# TDC_VTUNE_DAC.net
KiCad netlist of a schematic drawn in Altium Designer
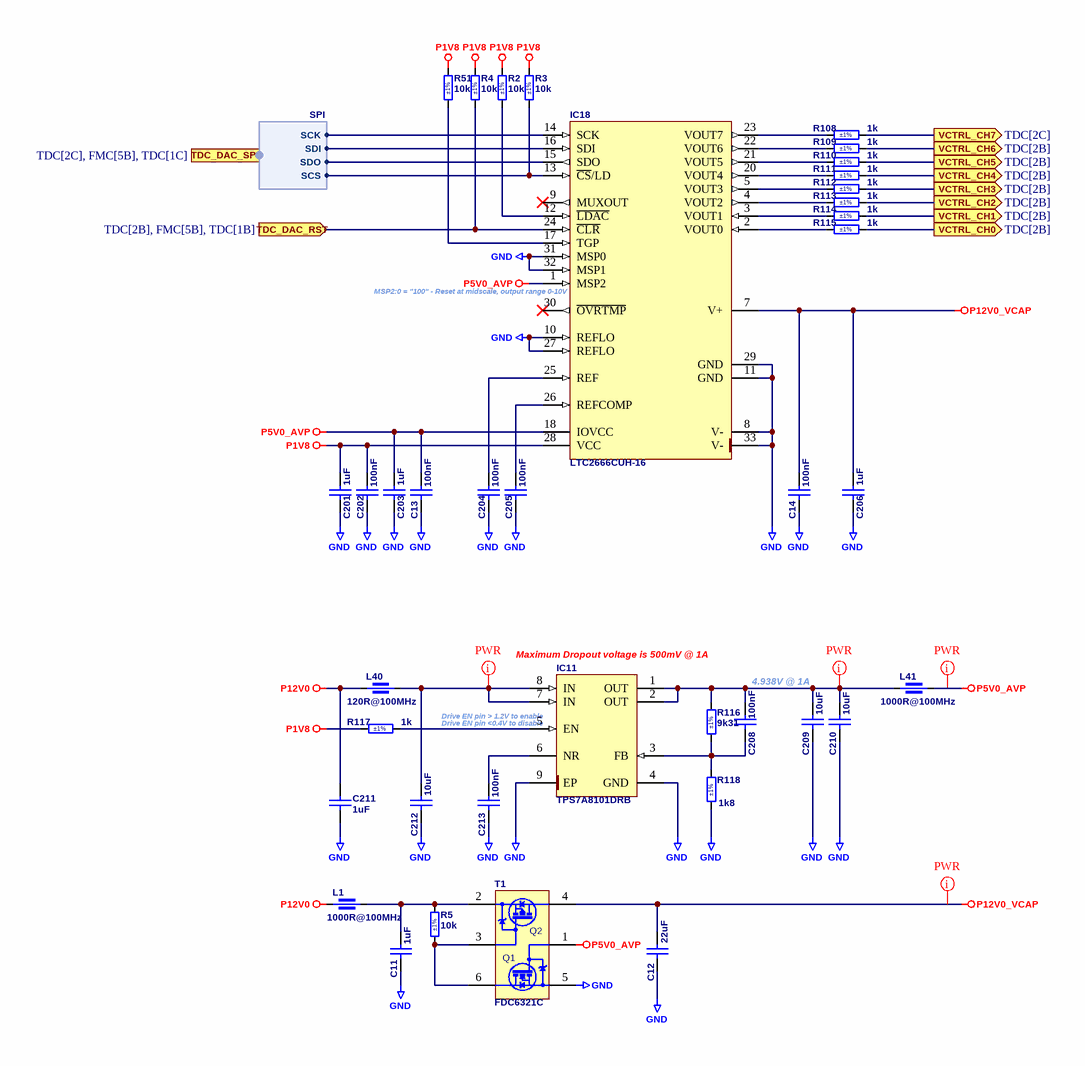
[diagram p0: TDC_VTUNE_DAC.SchDoc]

(export (version "E")
  (design (tool "Eeschema 10.0.6"))
  (components
    (comp (ref "C11")
      (value "1uF")
      (footprint "CAPC1005X55N")
      (description "Non-polarised capacitor")
      (fields
        (field (name "PART NUMBER") "CC0402_1UF_16V_10%_X5R")
        (field (name "VOLTAGE") "16V")
        (field (name "AUTHOR") "CERN DEM JLC")
      )
      (libsource (lib "Capacitors") (part "Capacitor - non polarized"))
    )
    (comp (ref "C12")
      (value "22uF")
      (footprint "CAPC2012X135N")
      (description "Non-polarised capacitor")
      (fields
        (field (name "MANUFACTURER PART NUMBER") "CC0805_22UF_16V_10%_X5R")
        (field (name "MANUFACTURER") "GENERIC")
        (field (name "AUTHOR") "CERN DEM JLC")
      )
      (libsource (lib "Capacitors") (part "Capacitor - non polarized"))
    )
    (comp (ref "C13")
      (value "100nF")
      (footprint "CAPC1005X55N")
      (description "Non-polarised capacitor")
      (fields
        (field (name "PART NUMBER") "CC0402_100NF_16V_10%_X5R")
        (field (name "VOLTAGE") "16V")
        (field (name "AUTHOR") "CERN DEM JLC")
      )
      (libsource (lib "Capacitors") (part "Capacitor - non polarized"))
    )
    (comp (ref "C14")
      (value "100nF")
      (footprint "CAPC1005X55N")
      (description "Non-polarised capacitor")
      (fields
        (field (name "PART NUMBER") "CC0402_100NF_16V_10%_X5R")
        (field (name "VOLTAGE") "16V")
        (field (name "AUTHOR") "CERN DEM JLC")
      )
      (libsource (lib "Capacitors") (part "Capacitor - non polarized"))
    )
    (comp (ref "C201")
      (value "1uF")
      (footprint "CAPC1608X87N")
      (description "Non-polarised capacitor")
      (fields
        (field (name "PART NUMBER") "CC0603_1UF_25V_10%_X7R")
        (field (name "VOLTAGE") "25V")
        (field (name "AUTHOR") "CERN DEM JLC")
      )
      (libsource (lib "Capacitors") (part "Capacitor - non polarized"))
    )
    (comp (ref "C202")
      (value "100nF")
      (footprint "CAPC1005X55N")
      (description "Non-polarised capacitor")
      (fields
        (field (name "PART NUMBER") "CC0402_100NF_16V_10%_X5R")
        (field (name "VOLTAGE") "16V")
        (field (name "AUTHOR") "CERN DEM JLC")
      )
      (libsource (lib "Capacitors") (part "Capacitor - non polarized"))
    )
    (comp (ref "C203")
      (value "1uF")
      (footprint "CAPC1608X87N")
      (description "Non-polarised capacitor")
      (fields
        (field (name "PART NUMBER") "CC0603_1UF_25V_10%_X7R")
        (field (name "VOLTAGE") "25V")
        (field (name "AUTHOR") "CERN DEM JLC")
      )
      (libsource (lib "Capacitors") (part "Capacitor - non polarized"))
    )
    (comp (ref "C204")
      (value "100nF")
      (footprint "CAPC1005X55N")
      (description "Non-polarised capacitor")
      (fields
        (field (name "PART NUMBER") "CC0402_100NF_16V_10%_X5R")
        (field (name "VOLTAGE") "16V")
        (field (name "AUTHOR") "CERN DEM JLC")
      )
      (libsource (lib "Capacitors") (part "Capacitor - non polarized"))
    )
    (comp (ref "C205")
      (value "100nF")
      (footprint "CAPC1005X55N")
      (description "Non-polarised capacitor")
      (fields
        (field (name "PART NUMBER") "CC0402_100NF_16V_10%_X5R")
        (field (name "VOLTAGE") "16V")
        (field (name "AUTHOR") "CERN DEM JLC")
      )
      (libsource (lib "Capacitors") (part "Capacitor - non polarized"))
    )
    (comp (ref "C206")
      (value "1uF")
      (footprint "CAPC1608X87N")
      (description "Non-polarised capacitor")
      (fields
        (field (name "PART NUMBER") "CC0603_1UF_25V_10%_X7R")
        (field (name "VOLTAGE") "25V")
        (field (name "AUTHOR") "CERN DEM JLC")
      )
      (libsource (lib "Capacitors") (part "Capacitor - non polarized"))
    )
    (comp (ref "C208")
      (value "100nF")
      (footprint "CAPC1005X55N")
      (description "Non-polarised capacitor")
      (fields
        (field (name "PART NUMBER") "CC0402_100NF_16V_10%_X5R")
        (field (name "VOLTAGE") "16V")
        (field (name "AUTHOR") "CERN DEM JLC")
      )
      (libsource (lib "Capacitors") (part "Capacitor - non polarized"))
    )
    (comp (ref "C209")
      (value "10uF")
      (footprint "CAPC1608X90N")
      (description "Non-polarised capacitor")
      (fields
        (field (name "PART NUMBER") "CC0603_10UF_16V_10%_X5R_MURATA_GRT188R61C106KE13")
        (field (name "VOLTAGE") "16V")
        (field (name "AUTHOR") "CERN DEM HF")
      )
      (libsource (lib "Capacitors") (part "Capacitor - non polarized"))
    )
    (comp (ref "C210")
      (value "10uF")
      (footprint "CAPC1608X90N")
      (description "Non-polarised capacitor")
      (fields
        (field (name "PART NUMBER") "CC0603_10UF_16V_10%_X5R_MURATA_GRT188R61C106KE13")
        (field (name "VOLTAGE") "16V")
        (field (name "AUTHOR") "CERN DEM HF")
      )
      (libsource (lib "Capacitors") (part "Capacitor - non polarized"))
    )
    (comp (ref "C211")
      (value "1uF")
      (footprint "CAPC1005X55N")
      (description "Non-polarised capacitor")
      (fields
        (field (name "PART NUMBER") "CC0402_1UF_16V_10%_X5R")
        (field (name "VOLTAGE") "16V")
        (field (name "AUTHOR") "CERN DEM JLC")
      )
      (libsource (lib "Capacitors") (part "Capacitor - non polarized"))
    )
    (comp (ref "C212")
      (value "10uF")
      (footprint "CAPC1608X90N")
      (description "Non-polarised capacitor")
      (fields
        (field (name "PART NUMBER") "CC0603_10UF_16V_10%_X5R_MURATA_GRT188R61C106KE13")
        (field (name "VOLTAGE") "16V")
        (field (name "AUTHOR") "CERN DEM HF")
      )
      (libsource (lib "Capacitors") (part "Capacitor - non polarized"))
    )
    (comp (ref "C213")
      (value "100nF")
      (footprint "CAPC1005X55N")
      (description "Non-polarised capacitor")
      (fields
        (field (name "PART NUMBER") "CC0402_100NF_16V_10%_X5R")
        (field (name "VOLTAGE") "16V")
        (field (name "AUTHOR") "CERN DEM JLC")
      )
      (libsource (lib "Capacitors") (part "Capacitor - non polarized"))
    )
    (comp (ref "IC11")
      (value "TPS7A8101DRB")
      (footprint "TEXAS_DRB(S-PVSON-N8)")
      (description "0.8V to 6V, 1A, Low-Noise, Wide-Bandwidth, High PSRR, Low-Dropout Linear Regulator")
      (fields (field (name "MANUFACTURER") "TEXAS INSTRUMENTS") (field (name "AUTHOR") "CERN DEM BC"))
      (libsource (lib "ICs And Semiconductors") (part "TPS7A8101DRB"))
    )
    (comp (ref "IC18")
      (value "LTC2666CUH-16")
      (footprint "QFN50P500X500X80-33N-S355")
      (description "Octal 16-Bit, ±10V Vout, SoftSpan DAC with 10ppm/°C Max Reference")
      (fields
        (field (name "PART NUMBER") "LTC2666CUH-16#PBF")
        (field (name "MANUFACTURER") "LINEAR TECHNOLOGY")
        (field (name "AUTHOR") "CERN DEM JLC")
      )
      (libsource (lib "ICs And Semiconductors") (part "LTC2666"))
    )
    (comp (ref "L1")
      (value "1000R@100MHz")
      (footprint "INDC1608X95N")
      (fields
        (field (name "PART NUMBER") "IND0603_MURATA_BLM18KG102SN1")
        (field (name "POWER") "1A")
        (field (name "TOLERANCE") "±25%")
        (field (name "AUTHOR") "CERN DEM HF")
      )
      (libsource (lib "Inductors & Transformers") (part "Ferrite Bead"))
    )
    (comp (ref "L40")
      (value "120R@100MHz")
      (footprint "INDC1005X55N")
      (fields
        (field (name "PART NUMBER") "IND0402_MURATA_BLM15PX121SN1D")
        (field (name "POWER") "2A")
        (field (name "TOLERANCE") "±25%")
        (field (name "AUTHOR") "CERN DEM JMW")
      )
      (libsource (lib "Inductors & Transformers") (part "Ferrite Bead"))
    )
    (comp (ref "L41")
      (value "1000R@100MHz")
      (footprint "INDC1608X95N")
      (fields
        (field (name "PART NUMBER") "IND0603_MURATA_BLM18KG102SN1")
        (field (name "POWER") "1A")
        (field (name "TOLERANCE") "±25%")
        (field (name "AUTHOR") "CERN DEM HF")
      )
      (libsource (lib "Inductors & Transformers") (part "Ferrite Bead"))
    )
    (comp (ref "R2")
      (value "10k")
      (footprint "RESC1005X40N")
      (description "Resistor - 1%")
      (fields
        (field (name "TOLERANCE") "±1%")
        (field (name "PART NUMBER") "R0402_10K_1%_0.0625W_100PPM")
        (field (name "POWER") "0.0625W")
        (field (name "AUTHOR") "CERN DEM JLC")
      )
      (libsource (lib "Resistors") (part "Resistor - 1%"))
    )
    (comp (ref "R3")
      (value "10k")
      (footprint "RESC1005X40N")
      (description "Resistor - 1%")
      (fields
        (field (name "TOLERANCE") "±1%")
        (field (name "PART NUMBER") "R0402_10K_1%_0.0625W_100PPM")
        (field (name "POWER") "0.0625W")
        (field (name "AUTHOR") "CERN DEM JLC")
      )
      (libsource (lib "Resistors") (part "Resistor - 1%"))
    )
    (comp (ref "R4")
      (value "10k")
      (footprint "RESC1005X40N")
      (description "Resistor - 1%")
      (fields
        (field (name "TOLERANCE") "±1%")
        (field (name "PART NUMBER") "R0402_10K_1%_0.0625W_100PPM")
        (field (name "POWER") "0.0625W")
        (field (name "AUTHOR") "CERN DEM JLC")
      )
      (libsource (lib "Resistors") (part "Resistor - 1%"))
    )
    (comp (ref "R5")
      (value "10k")
      (footprint "RESC1005X40N")
      (description "Resistor - 1%")
      (fields
        (field (name "TOLERANCE") "±1%")
        (field (name "PART NUMBER") "R0402_10K_1%_0.0625W_100PPM")
        (field (name "POWER") "0.0625W")
        (field (name "AUTHOR") "CERN DEM JLC")
      )
      (libsource (lib "Resistors") (part "Resistor - 1%"))
    )
    (comp (ref "R51")
      (value "10k")
      (footprint "RESC1005X40N")
      (description "Resistor - 1%")
      (fields
        (field (name "TOLERANCE") "±1%")
        (field (name "PART NUMBER") "R0402_10K_1%_0.0625W_100PPM")
        (field (name "POWER") "0.0625W")
        (field (name "AUTHOR") "CERN DEM JLC")
      )
      (libsource (lib "Resistors") (part "Resistor - 1%"))
    )
    (comp (ref "R108")
      (value "1k")
      (footprint "RESC1005X40N")
      (description "Resistor - 1%")
      (fields
        (field (name "TOLERANCE") "±1%")
        (field (name "PART NUMBER") "R0402_1K_1%_0.0625W_100PPM")
        (field (name "POWER") "0.0625W")
        (field (name "AUTHOR") "CERN DEM JLC")
      )
      (libsource (lib "Resistors") (part "Resistor - 1%"))
    )
    (comp (ref "R109")
      (value "1k")
      (footprint "RESC1005X40N")
      (description "Resistor - 1%")
      (fields
        (field (name "TOLERANCE") "±1%")
        (field (name "PART NUMBER") "R0402_1K_1%_0.0625W_100PPM")
        (field (name "POWER") "0.0625W")
        (field (name "AUTHOR") "CERN DEM JLC")
      )
      (libsource (lib "Resistors") (part "Resistor - 1%"))
    )
    (comp (ref "R110")
      (value "1k")
      (footprint "RESC1005X40N")
      (description "Resistor - 1%")
      (fields
        (field (name "TOLERANCE") "±1%")
        (field (name "PART NUMBER") "R0402_1K_1%_0.0625W_100PPM")
        (field (name "POWER") "0.0625W")
        (field (name "AUTHOR") "CERN DEM JLC")
      )
      (libsource (lib "Resistors") (part "Resistor - 1%"))
    )
    (comp (ref "R111")
      (value "1k")
      (footprint "RESC1005X40N")
      (description "Resistor - 1%")
      (fields
        (field (name "TOLERANCE") "±1%")
        (field (name "PART NUMBER") "R0402_1K_1%_0.0625W_100PPM")
        (field (name "POWER") "0.0625W")
        (field (name "AUTHOR") "CERN DEM JLC")
      )
      (libsource (lib "Resistors") (part "Resistor - 1%"))
    )
    (comp (ref "R112")
      (value "1k")
      (footprint "RESC1005X40N")
      (description "Resistor - 1%")
      (fields
        (field (name "TOLERANCE") "±1%")
        (field (name "PART NUMBER") "R0402_1K_1%_0.0625W_100PPM")
        (field (name "POWER") "0.0625W")
        (field (name "AUTHOR") "CERN DEM JLC")
      )
      (libsource (lib "Resistors") (part "Resistor - 1%"))
    )
    (comp (ref "R113")
      (value "1k")
      (footprint "RESC1005X40N")
      (description "Resistor - 1%")
      (fields
        (field (name "TOLERANCE") "±1%")
        (field (name "PART NUMBER") "R0402_1K_1%_0.0625W_100PPM")
        (field (name "POWER") "0.0625W")
        (field (name "AUTHOR") "CERN DEM JLC")
      )
      (libsource (lib "Resistors") (part "Resistor - 1%"))
    )
    (comp (ref "R114")
      (value "1k")
      (footprint "RESC1005X40N")
      (description "Resistor - 1%")
      (fields
        (field (name "TOLERANCE") "±1%")
        (field (name "PART NUMBER") "R0402_1K_1%_0.0625W_100PPM")
        (field (name "POWER") "0.0625W")
        (field (name "AUTHOR") "CERN DEM JLC")
      )
      (libsource (lib "Resistors") (part "Resistor - 1%"))
    )
    (comp (ref "R115")
      (value "1k")
      (footprint "RESC1005X40N")
      (description "Resistor - 1%")
      (fields
        (field (name "TOLERANCE") "±1%")
        (field (name "PART NUMBER") "R0402_1K_1%_0.0625W_100PPM")
        (field (name "POWER") "0.0625W")
        (field (name "AUTHOR") "CERN DEM JLC")
      )
      (libsource (lib "Resistors") (part "Resistor - 1%"))
    )
    (comp (ref "R116")
      (value "9k31")
      (footprint "RESC1005X40N")
      (description "Resistor - 1%")
      (fields
        (field (name "TOLERANCE") "±1%")
        (field (name "PART NUMBER") "R0402_9K31_1%_0.0625W_100PPM")
        (field (name "POWER") "0.0625W")
        (field (name "AUTHOR") "CERN DEM JMW")
      )
      (libsource (lib "Resistors") (part "Resistor - 1%"))
    )
    (comp (ref "R117")
      (value "1k")
      (footprint "RESC1005X40N")
      (description "Resistor - 1%")
      (fields
        (field (name "TOLERANCE") "±1%")
        (field (name "PART NUMBER") "R0402_1K_1%_0.0625W_100PPM")
        (field (name "POWER") "0.0625W")
        (field (name "AUTHOR") "CERN DEM JLC")
      )
      (libsource (lib "Resistors") (part "Resistor - 1%"))
    )
    (comp (ref "R118")
      (value "1k8")
      (footprint "RESC1005X40N")
      (description "Resistor - 1%")
      (fields
        (field (name "TOLERANCE") "±1%")
        (field (name "PART NUMBER") "R0402_1K8_1%_0.0625W_100PPM")
        (field (name "POWER") "0.0625W")
        (field (name "AUTHOR") "CERN DEM JLC")
      )
      (libsource (lib "Resistors") (part "Resistor - 1%"))
    )
    (comp (ref "T1")
      (value "FDC6321C")
      (footprint "SOT95P280X110-6N")
      (description "25V, 680mA N-Channel, and -25V, -460mA P-Channel, Dual Digital FET")
      (fields (field (name "MANUFACTURER") "ON SEMICONDUCTOR") (field (name "AUTHOR") "CERN DEM BC"))
      (libsource (lib "ICs And Semiconductors") (part "FDC6321C"))
    )
  )
  (nets
    (net (code "2") (name "/SCK") (class "Default")
      (node (ref "IC18") (pin "14") (pinfunction "SCK_14") (pintype "input"))
    )
    (net (code "3") (name "/SCS") (class "Default")
      (node (ref "IC18") (pin "13") (pinfunction "~{CS}/LD_13") (pintype "input"))
      (node (ref "R3") (pin "1") (pinfunction "1_1") (pintype "passive"))
    )
    (net (code "4") (name "/SDI") (class "Default")
      (node (ref "IC18") (pin "16") (pinfunction "SDI_16") (pintype "input"))
    )
    (net (code "5") (name "/SDO") (class "Default")
      (node (ref "IC18") (pin "15") (pinfunction "SDO_15") (pintype "output"))
    )
    (net (code "6") (name "/TDC_DAC_RST") (class "Default")
      (node (ref "IC18") (pin "24") (pinfunction "~{CLR}_24") (pintype "input"))
      (node (ref "R4") (pin "1") (pinfunction "1_1") (pintype "passive"))
    )
    (net (code "7") (name "/VCTRL_CH0") (class "Default")
      (node (ref "R115") (pin "2") (pinfunction "2_2") (pintype "passive"))
    )
    (net (code "8") (name "/VCTRL_CH1") (class "Default")
      (node (ref "R114") (pin "2") (pinfunction "2_2") (pintype "passive"))
    )
    (net (code "9") (name "/VCTRL_CH2") (class "Default")
      (node (ref "R113") (pin "2") (pinfunction "2_2") (pintype "passive"))
    )
    (net (code "10") (name "/VCTRL_CH3") (class "Default")
      (node (ref "R112") (pin "2") (pinfunction "2_2") (pintype "passive"))
    )
    (net (code "11") (name "/VCTRL_CH4") (class "Default")
      (node (ref "R111") (pin "2") (pinfunction "2_2") (pintype "passive"))
    )
    (net (code "12") (name "/VCTRL_CH5") (class "Default")
      (node (ref "R110") (pin "2") (pinfunction "2_2") (pintype "passive"))
    )
    (net (code "13") (name "/VCTRL_CH6") (class "Default")
      (node (ref "R109") (pin "2") (pinfunction "2_2") (pintype "passive"))
    )
    (net (code "14") (name "/VCTRL_CH7") (class "Default")
      (node (ref "R108") (pin "2") (pinfunction "2_2") (pintype "passive"))
    )
    (net (code "16") (name "GND") (class "Default")
      (node (ref "C11") (pin "1") (pinfunction "1_1") (pintype "passive"))
      (node (ref "C12") (pin "1") (pinfunction "1_1") (pintype "passive"))
      (node (ref "C13") (pin "1") (pinfunction "1_1") (pintype "passive"))
      (node (ref "C14") (pin "1") (pinfunction "1_1") (pintype "passive"))
      (node (ref "C201") (pin "1") (pinfunction "1_1") (pintype "passive"))
      (node (ref "C202") (pin "1") (pinfunction "1_1") (pintype "passive"))
      (node (ref "C203") (pin "1") (pinfunction "1_1") (pintype "passive"))
      (node (ref "C204") (pin "1") (pinfunction "1_1") (pintype "passive"))
      (node (ref "C205") (pin "1") (pinfunction "1_1") (pintype "passive"))
      (node (ref "C206") (pin "1") (pinfunction "1_1") (pintype "passive"))
      (node (ref "C209") (pin "1") (pinfunction "1_1") (pintype "passive"))
      (node (ref "C210") (pin "1") (pinfunction "1_1") (pintype "passive"))
      (node (ref "C211") (pin "1") (pinfunction "1_1") (pintype "passive"))
      (node (ref "C212") (pin "1") (pinfunction "1_1") (pintype "passive"))
      (node (ref "C213") (pin "1") (pinfunction "1_1") (pintype "passive"))
      (node (ref "IC11") (pin "4") (pinfunction "GND_4") (pintype "power_in"))
      (node (ref "IC11") (pin "9") (pinfunction "EP_9") (pintype "power_in"))
      (node (ref "IC18") (pin "10") (pinfunction "REFLO_10") (pintype "input"))
      (node (ref "IC18") (pin "11") (pinfunction "GND_11") (pintype "power_in"))
      (node (ref "IC18") (pin "27") (pinfunction "REFLO_27") (pintype "input"))
      (node (ref "IC18") (pin "29") (pinfunction "GND_29") (pintype "power_in"))
      (node (ref "IC18") (pin "31") (pinfunction "MSP0_31") (pintype "input"))
      (node (ref "IC18") (pin "32") (pinfunction "MSP1_32") (pintype "input"))
      (node (ref "IC18") (pin "33") (pinfunction "V-_33") (pintype "power_in"))
      (node (ref "IC18") (pin "8") (pinfunction "V-_8") (pintype "power_in"))
      (node (ref "R118") (pin "1") (pinfunction "1_1") (pintype "passive"))
      (node (ref "T1") (pin "5") (pinfunction "S1_5") (pintype "passive"))
    )
    (net (code "17") (name "Net-(C208-Pad2)") (class "Default")
      (node (ref "C208") (pin "2") (pinfunction "2_2") (pintype "passive"))
      (node (ref "C209") (pin "2") (pinfunction "2_2") (pintype "passive"))
      (node (ref "C210") (pin "2") (pinfunction "2_2") (pintype "passive"))
      (node (ref "IC11") (pin "1") (pinfunction "OUT_1") (pintype "power_in"))
      (node (ref "IC11") (pin "2") (pinfunction "OUT_2") (pintype "power_in"))
      (node (ref "L41") (pin "1") (pinfunction "1_1") (pintype "passive"))
      (node (ref "R116") (pin "2") (pinfunction "2_2") (pintype "passive"))
    )
    (net (code "18") (name "Net-(C212-Pad2)") (class "Default")
      (node (ref "C212") (pin "2") (pinfunction "2_2") (pintype "passive"))
      (node (ref "IC11") (pin "7") (pinfunction "IN_7") (pintype "input"))
      (node (ref "IC11") (pin "8") (pinfunction "IN_8") (pintype "input"))
      (node (ref "L40") (pin "2") (pinfunction "2_2") (pintype "passive"))
    )
    (net (code "19") (name "Net-(IC11-EN)") (class "Default")
      (node (ref "IC11") (pin "5") (pinfunction "EN_5") (pintype "input"))
      (node (ref "R117") (pin "2") (pinfunction "2_2") (pintype "passive"))
    )
    (net (code "20") (name "Net-(IC11-FB)") (class "Default")
      (node (ref "C208") (pin "1") (pinfunction "1_1") (pintype "passive"))
      (node (ref "IC11") (pin "3") (pinfunction "FB_3") (pintype "input"))
      (node (ref "R116") (pin "1") (pinfunction "1_1") (pintype "passive"))
      (node (ref "R118") (pin "2") (pinfunction "2_2") (pintype "passive"))
    )
    (net (code "21") (name "Net-(IC11-NR)") (class "Default")
      (node (ref "C213") (pin "2") (pinfunction "2_2") (pintype "passive"))
      (node (ref "IC11") (pin "6") (pinfunction "NR_6") (pintype "passive"))
    )
    (net (code "22") (name "Net-(IC18-REF)") (class "Default")
      (node (ref "C204") (pin "2") (pinfunction "2_2") (pintype "passive"))
      (node (ref "IC18") (pin "25") (pinfunction "REF_25") (pintype "input"))
    )
    (net (code "23") (name "Net-(IC18-REFCOMP)") (class "Default")
      (node (ref "C205") (pin "2") (pinfunction "2_2") (pintype "passive"))
      (node (ref "IC18") (pin "26") (pinfunction "REFCOMP_26") (pintype "input"))
    )
    (net (code "24") (name "Net-(IC18-TGP)") (class "Default")
      (node (ref "IC18") (pin "17") (pinfunction "TGP_17") (pintype "input"))
      (node (ref "R51") (pin "1") (pinfunction "1_1") (pintype "passive"))
    )
    (net (code "25") (name "Net-(IC18-VOUT0)") (class "Default")
      (node (ref "IC18") (pin "2") (pinfunction "VOUT0_2") (pintype "input"))
      (node (ref "R115") (pin "1") (pinfunction "1_1") (pintype "passive"))
    )
    (net (code "26") (name "Net-(IC18-VOUT1)") (class "Default")
      (node (ref "IC18") (pin "3") (pinfunction "VOUT1_3") (pintype "input"))
      (node (ref "R114") (pin "1") (pinfunction "1_1") (pintype "passive"))
    )
    (net (code "27") (name "Net-(IC18-VOUT2)") (class "Default")
      (node (ref "IC18") (pin "4") (pinfunction "VOUT2_4") (pintype "output"))
      (node (ref "R113") (pin "1") (pinfunction "1_1") (pintype "passive"))
    )
    (net (code "28") (name "Net-(IC18-VOUT3)") (class "Default")
      (node (ref "IC18") (pin "5") (pinfunction "VOUT3_5") (pintype "output"))
      (node (ref "R112") (pin "1") (pinfunction "1_1") (pintype "passive"))
    )
    (net (code "29") (name "Net-(IC18-VOUT4)") (class "Default")
      (node (ref "IC18") (pin "20") (pinfunction "VOUT4_20") (pintype "output"))
      (node (ref "R111") (pin "1") (pinfunction "1_1") (pintype "passive"))
    )
    (net (code "30") (name "Net-(IC18-VOUT5)") (class "Default")
      (node (ref "IC18") (pin "21") (pinfunction "VOUT5_21") (pintype "output"))
      (node (ref "R110") (pin "1") (pinfunction "1_1") (pintype "passive"))
    )
    (net (code "31") (name "Net-(IC18-VOUT6)") (class "Default")
      (node (ref "IC18") (pin "22") (pinfunction "VOUT6_22") (pintype "output"))
      (node (ref "R109") (pin "1") (pinfunction "1_1") (pintype "passive"))
    )
    (net (code "32") (name "Net-(IC18-VOUT7)") (class "Default")
      (node (ref "IC18") (pin "23") (pinfunction "VOUT7_23") (pintype "output"))
      (node (ref "R108") (pin "1") (pinfunction "1_1") (pintype "passive"))
    )
    (net (code "33") (name "Net-(IC18-~{LDAC})") (class "Default")
      (node (ref "IC18") (pin "12") (pinfunction "~{LDAC}_12") (pintype "input"))
      (node (ref "R2") (pin "1") (pinfunction "1_1") (pintype "passive"))
    )
    (net (code "34") (name "Net-(T1-D1)") (class "Default")
      (node (ref "R5") (pin "1") (pinfunction "1_1") (pintype "passive"))
      (node (ref "T1") (pin "3") (pinfunction "G2_3") (pintype "passive"))
      (node (ref "T1") (pin "6") (pinfunction "D1_6") (pintype "passive"))
    )
    (net (code "35") (name "Net-(T1-S2)") (class "Default")
      (node (ref "C11") (pin "2") (pinfunction "2_2") (pintype "passive"))
      (node (ref "L1") (pin "2") (pinfunction "2_2") (pintype "passive"))
      (node (ref "R5") (pin "2") (pinfunction "2_2") (pintype "passive"))
      (node (ref "T1") (pin "2") (pinfunction "S2_2") (pintype "passive"))
    )
    (net (code "36") (name "P1V8") (class "Default")
      (node (ref "C201") (pin "2") (pinfunction "2_2") (pintype "passive"))
      (node (ref "C202") (pin "2") (pinfunction "2_2") (pintype "passive"))
      (node (ref "IC18") (pin "28") (pinfunction "VCC_28") (pintype "power_in"))
      (node (ref "R117") (pin "1") (pinfunction "1_1") (pintype "passive"))
      (node (ref "R2") (pin "2") (pinfunction "2_2") (pintype "passive"))
      (node (ref "R3") (pin "2") (pinfunction "2_2") (pintype "passive"))
      (node (ref "R4") (pin "2") (pinfunction "2_2") (pintype "passive"))
      (node (ref "R51") (pin "2") (pinfunction "2_2") (pintype "passive"))
    )
    (net (code "37") (name "P5V0_AVP") (class "Default")
      (node (ref "C13") (pin "2") (pinfunction "2_2") (pintype "passive"))
      (node (ref "C203") (pin "2") (pinfunction "2_2") (pintype "passive"))
      (node (ref "IC18") (pin "1") (pinfunction "MSP2_1") (pintype "input"))
      (node (ref "IC18") (pin "18") (pinfunction "IOVCC_18") (pintype "power_in"))
      (node (ref "L41") (pin "2") (pinfunction "2_2") (pintype "passive"))
      (node (ref "T1") (pin "1") (pinfunction "G1_1") (pintype "passive"))
    )
    (net (code "38") (name "P12V0") (class "Default")
      (node (ref "C211") (pin "2") (pinfunction "2_2") (pintype "passive"))
      (node (ref "L1") (pin "1") (pinfunction "1_1") (pintype "passive"))
      (node (ref "L40") (pin "1") (pinfunction "1_1") (pintype "passive"))
    )
    (net (code "39") (name "P12V0_VCAP") (class "Default")
      (node (ref "C12") (pin "2") (pinfunction "2_2") (pintype "passive"))
      (node (ref "C14") (pin "2") (pinfunction "2_2") (pintype "passive"))
      (node (ref "C206") (pin "2") (pinfunction "2_2") (pintype "passive"))
      (node (ref "IC18") (pin "7") (pinfunction "V+_7") (pintype "power_in"))
      (node (ref "T1") (pin "4") (pinfunction "D2_4") (pintype "passive"))
    )
    (net (code "40") (name "unconnected-(IC18-MUXOUT-Pad9)") (class "Default")
      (node (ref "IC18") (pin "9") (pinfunction "MUXOUT_9") (pintype "output+no_connect"))
    )
    (net (code "41") (name "unconnected-(IC18-~{OVRTMP}-Pad30)") (class "Default")
      (node (ref "IC18") (pin "30") (pinfunction "~{OVRTMP}_30") (pintype "output+no_connect"))
    )
  )
)
